# design.net
KiCad netlist of a schematic drawn in Altium Designer
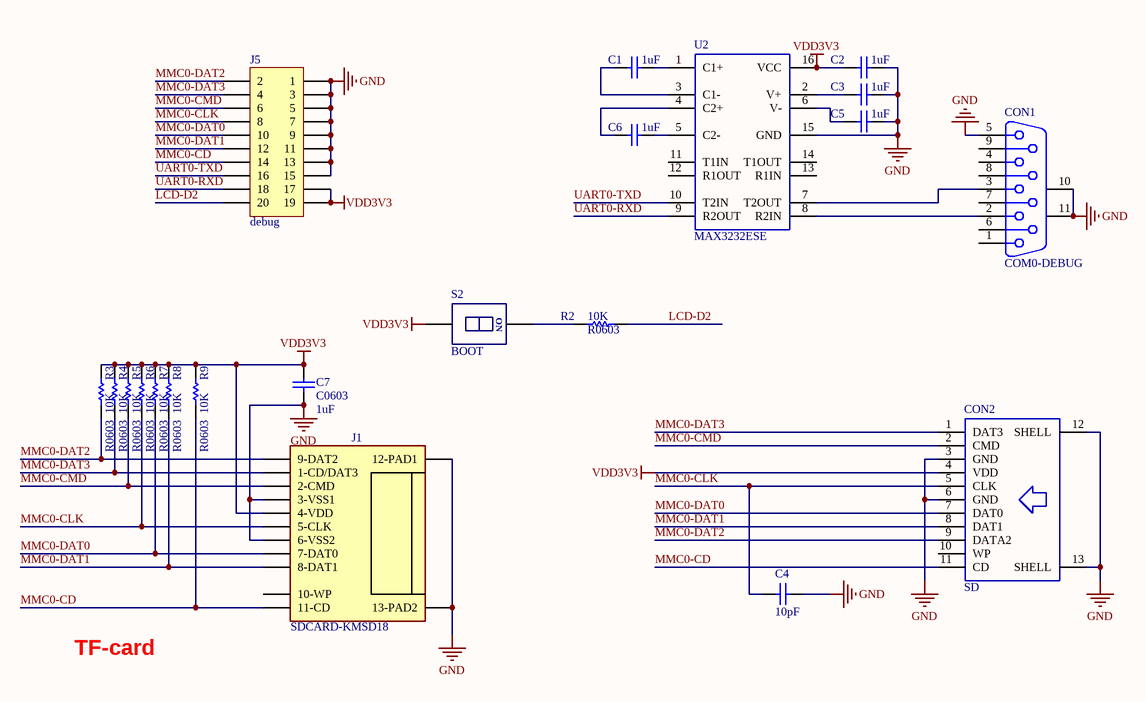
[diagram p0: 调试烧写.SchDoc]

(export (version "E")
  (design (tool "Eeschema 10.0.6"))
  (components
    (comp (ref "C1")
      (value "1uF")
      (footprint "C0603_M1608")
      (description "Capacitor")
      (fields (field (name "Comment") "Cap") (field (name "PUBLISHER") "Altium Limited"))
      (libsource (lib "Miscellaneous Devices") (part "Cap"))
    )
    (comp (ref "C2")
      (value "1uF")
      (footprint "C0603_M1608")
      (description "Capacitor")
      (fields (field (name "Comment") "Cap") (field (name "PUBLISHER") "Altium Limited"))
      (libsource (lib "Miscellaneous Devices") (part "Cap"))
    )
    (comp (ref "C3")
      (value "1uF")
      (footprint "C0603_M1608")
      (description "Capacitor")
      (fields (field (name "Comment") "Cap") (field (name "PUBLISHER") "Altium Limited"))
      (libsource (lib "Miscellaneous Devices") (part "Cap"))
    )
    (comp (ref "C4")
      (value "10pF")
      (footprint "C0603_M1608")
      (description "Capacitor")
      (fields (field (name "Comment") "Cap") (field (name "PUBLISHER") "Altium Limited"))
      (libsource (lib "Miscellaneous Devices") (part "Cap"))
    )
    (comp (ref "C5")
      (value "1uF")
      (footprint "C0603_M1608")
      (description "Capacitor")
      (fields (field (name "Comment") "Cap") (field (name "PUBLISHER") "Altium Limited"))
      (libsource (lib "Miscellaneous Devices") (part "Cap"))
    )
    (comp (ref "C6")
      (value "1uF")
      (footprint "C0603_M1608")
      (description "Capacitor")
      (fields (field (name "Comment") "Cap") (field (name "PUBLISHER") "Altium Limited"))
      (libsource (lib "Miscellaneous Devices") (part "Cap"))
    )
    (comp (ref "C7")
      (value "C0603")
      (description "Capacitor")
      (fields (field (name "ALTIUM_VALUE") "1uF") (field (name "PUBLISHER") "Altium Limited"))
      (libsource (lib "Miscellaneous Devices") (part "Cap"))
    )
    (comp (ref "CON1")
      (value "COM0-DEBUG")
      (footprint "DSUB1.385-2H9-M")
      (description "Receptacle Assembly, 9 Position, Right Angle")
      (fields (field (name "PUBLISHER") "Altium Limited"))
      (libsource (lib "Miscellaneous Connectors") (part "D Connector 9"))
    )
    (comp (ref "CON2") (value "SD") (footprint "SD-CARD3") (libsource (lib "Sch") (part "SD")))
    (comp (ref "J1")
      (value "SDCARD-KMSD18")
      (footprint "TF-CARD")
      (libsource (lib "Miscellaneous Connectors") (part "SDCARD_KMSD18"))
    )
    (comp (ref "J5")
      (value "debug")
      (description "Header, 10-Pin, Dual row")
      (fields (field (name "PUBLISHER") "Altium Limited"))
      (libsource (lib "Miscellaneous Connectors") (part "Header 10X2"))
    )
    (comp (ref "R2")
      (value "R0603")
      (description "Resistor")
      (fields (field (name "ALTIUM_VALUE") "10K") (field (name "PUBLISHER") "Altium Limited"))
      (libsource (lib "Miscellaneous Devices") (part "Res1"))
    )
    (comp (ref "R3")
      (value "R0603")
      (description "Resistor")
      (fields (field (name "ALTIUM_VALUE") "10K") (field (name "PUBLISHER") "Altium Limited"))
      (libsource (lib "Miscellaneous Devices") (part "Res1"))
    )
    (comp (ref "R4")
      (value "R0603")
      (description "Resistor")
      (fields (field (name "ALTIUM_VALUE") "10K") (field (name "PUBLISHER") "Altium Limited"))
      (libsource (lib "Miscellaneous Devices") (part "Res1"))
    )
    (comp (ref "R5")
      (value "R0603")
      (description "Resistor")
      (fields (field (name "ALTIUM_VALUE") "10K") (field (name "PUBLISHER") "Altium Limited"))
      (libsource (lib "Miscellaneous Devices") (part "Res1"))
    )
    (comp (ref "R6")
      (value "R0603")
      (description "Resistor")
      (fields (field (name "ALTIUM_VALUE") "10K") (field (name "PUBLISHER") "Altium Limited"))
      (libsource (lib "Miscellaneous Devices") (part "Res1"))
    )
    (comp (ref "R7")
      (value "R0603")
      (description "Resistor")
      (fields (field (name "ALTIUM_VALUE") "10K") (field (name "PUBLISHER") "Altium Limited"))
      (libsource (lib "Miscellaneous Devices") (part "Res1"))
    )
    (comp (ref "R8")
      (value "R0603")
      (description "Resistor")
      (fields (field (name "ALTIUM_VALUE") "10K") (field (name "PUBLISHER") "Altium Limited"))
      (libsource (lib "Miscellaneous Devices") (part "Res1"))
    )
    (comp (ref "R9")
      (value "R0603")
      (description "Resistor")
      (fields (field (name "ALTIUM_VALUE") "10K") (field (name "PUBLISHER") "Altium Limited"))
      (libsource (lib "Miscellaneous Devices") (part "Res1"))
    )
    (comp (ref "S2")
      (value "BOOT")
      (footprint "SWITCH_1P")
      (libsource (lib "Miscellaneous Connectors") (part "SW DIP-1"))
    )
    (comp (ref "U2") (value "MAX3232ESE") (footprint "SOIC-16N") (libsource (lib "Sch") (part "MAX3232")))
  )
  (nets
    (net (code "1") (name "/LCD-D2") (class "Default")
      (node (ref "J5") (pin "20") (pinfunction "20_20") (pintype "passive"))
      (node (ref "R2") (pin "2") (pinfunction "2_2") (pintype "passive"))
    )
    (net (code "2") (name "/MMC0-CD") (class "Default")
      (node (ref "CON2") (pin "11") (pinfunction "CD_11") (pintype "passive"))
      (node (ref "J1") (pin "11") (pinfunction "11-CD_11") (pintype "passive"))
      (node (ref "J5") (pin "14") (pinfunction "14_14") (pintype "passive"))
      (node (ref "R9") (pin "1") (pinfunction "1_1") (pintype "passive"))
    )
    (net (code "3") (name "/MMC0-CLK") (class "Default")
      (node (ref "C4") (pin "2") (pinfunction "2_2") (pintype "passive"))
      (node (ref "CON2") (pin "5") (pinfunction "CLK_5") (pintype "passive"))
      (node (ref "J1") (pin "5") (pinfunction "5-CLK_5") (pintype "passive"))
      (node (ref "J5") (pin "8") (pinfunction "8_8") (pintype "passive"))
      (node (ref "R6") (pin "1") (pinfunction "1_1") (pintype "passive"))
    )
    (net (code "4") (name "/MMC0-CMD") (class "Default")
      (node (ref "CON2") (pin "2") (pinfunction "CMD_2") (pintype "passive"))
      (node (ref "J1") (pin "2") (pinfunction "2-CMD_2") (pintype "passive"))
      (node (ref "J5") (pin "6") (pinfunction "6_6") (pintype "passive"))
      (node (ref "R5") (pin "1") (pinfunction "1_1") (pintype "passive"))
    )
    (net (code "5") (name "/MMC0-DAT0") (class "Default")
      (node (ref "CON2") (pin "7") (pinfunction "DAT0_7") (pintype "passive"))
      (node (ref "J1") (pin "7") (pinfunction "7-DAT0_7") (pintype "passive"))
      (node (ref "J5") (pin "10") (pinfunction "10_10") (pintype "passive"))
      (node (ref "R7") (pin "1") (pinfunction "1_1") (pintype "passive"))
    )
    (net (code "6") (name "/MMC0-DAT1") (class "Default")
      (node (ref "CON2") (pin "8") (pinfunction "DAT1_8") (pintype "passive"))
      (node (ref "J1") (pin "8") (pinfunction "8-DAT1_8") (pintype "passive"))
      (node (ref "J5") (pin "12") (pinfunction "12_12") (pintype "passive"))
      (node (ref "R8") (pin "1") (pinfunction "1_1") (pintype "passive"))
    )
    (net (code "7") (name "/MMC0-DAT2") (class "Default")
      (node (ref "CON2") (pin "9") (pinfunction "DATA2_9") (pintype "passive"))
      (node (ref "J1") (pin "9") (pinfunction "9-DAT2_9") (pintype "passive"))
      (node (ref "J5") (pin "2") (pinfunction "2_2") (pintype "passive"))
      (node (ref "R3") (pin "1") (pinfunction "1_1") (pintype "passive"))
    )
    (net (code "8") (name "/MMC0-DAT3") (class "Default")
      (node (ref "CON2") (pin "1") (pinfunction "DAT3_1") (pintype "passive"))
      (node (ref "J1") (pin "1") (pinfunction "1-CD/DAT3_1") (pintype "passive"))
      (node (ref "J5") (pin "4") (pinfunction "4_4") (pintype "passive"))
      (node (ref "R4") (pin "1") (pinfunction "1_1") (pintype "passive"))
    )
    (net (code "9") (name "/UART0-RXD") (class "Default")
      (node (ref "J5") (pin "18") (pinfunction "18_18") (pintype "passive"))
      (node (ref "U2") (pin "9") (pinfunction "R2OUT_9") (pintype "passive"))
    )
    (net (code "10") (name "/UART0-TXD") (class "Default")
      (node (ref "J5") (pin "16") (pinfunction "16_16") (pintype "passive"))
      (node (ref "U2") (pin "10") (pinfunction "T2IN_10") (pintype "passive"))
    )
    (net (code "11") (name "GND") (class "Default")
      (node (ref "C2") (pin "1") (pinfunction "1_1") (pintype "passive"))
      (node (ref "C3") (pin "1") (pinfunction "1_1") (pintype "passive"))
      (node (ref "C4") (pin "1") (pinfunction "1_1") (pintype "passive"))
      (node (ref "C5") (pin "1") (pinfunction "1_1") (pintype "passive"))
      (node (ref "C7") (pin "1") (pinfunction "1_1") (pintype "passive"))
      (node (ref "CON1") (pin "10") (pinfunction "MH1_10") (pintype "passive"))
      (node (ref "CON1") (pin "11") (pinfunction "MH2_11") (pintype "passive"))
      (node (ref "CON1") (pin "5") (pinfunction "5_5") (pintype "passive"))
      (node (ref "CON2") (pin "12") (pinfunction "SHELL_12") (pintype "passive"))
      (node (ref "CON2") (pin "13") (pinfunction "SHELL_13") (pintype "passive"))
      (node (ref "CON2") (pin "3") (pinfunction "GND_3") (pintype "passive"))
      (node (ref "CON2") (pin "6") (pinfunction "GND_6") (pintype "passive"))
      (node (ref "J1") (pin "12") (pinfunction "12-PAD1_12") (pintype "passive"))
      (node (ref "J1") (pin "13") (pinfunction "13-PAD2_13") (pintype "passive"))
      (node (ref "J1") (pin "3") (pinfunction "3-VSS1_3") (pintype "passive"))
      (node (ref "J1") (pin "6") (pinfunction "6-VSS2_6") (pintype "passive"))
      (node (ref "J5") (pin "1") (pinfunction "1_1") (pintype "passive"))
      (node (ref "J5") (pin "11") (pinfunction "11_11") (pintype "passive"))
      (node (ref "J5") (pin "13") (pinfunction "13_13") (pintype "passive"))
      (node (ref "J5") (pin "15") (pinfunction "15_15") (pintype "passive"))
      (node (ref "J5") (pin "3") (pinfunction "3_3") (pintype "passive"))
      (node (ref "J5") (pin "5") (pinfunction "5_5") (pintype "passive"))
      (node (ref "J5") (pin "7") (pinfunction "7_7") (pintype "passive"))
      (node (ref "J5") (pin "9") (pinfunction "9_9") (pintype "passive"))
      (node (ref "U2") (pin "15") (pinfunction "GND_15") (pintype "passive"))
    )
    (net (code "12") (name "Net-(R2-Pad1)") (class "Default")
      (node (ref "R2") (pin "1") (pinfunction "1_1") (pintype "passive"))
      (node (ref "S2") (pin "2") (pinfunction "2_2") (pintype "passive"))
    )
    (net (code "13") (name "Net-(U2-C1+)") (class "Default")
      (node (ref "C1") (pin "1") (pinfunction "1_1") (pintype "passive"))
      (node (ref "U2") (pin "1") (pinfunction "C1+_1") (pintype "passive"))
    )
    (net (code "14") (name "Net-(U2-C1-)") (class "Default")
      (node (ref "C1") (pin "2") (pinfunction "2_2") (pintype "passive"))
      (node (ref "U2") (pin "3") (pinfunction "C1-_3") (pintype "passive"))
    )
    (net (code "15") (name "Net-(U2-C2+)") (class "Default")
      (node (ref "C6") (pin "2") (pinfunction "2_2") (pintype "passive"))
      (node (ref "U2") (pin "4") (pinfunction "C2+_4") (pintype "passive"))
    )
    (net (code "16") (name "Net-(U2-C2-)") (class "Default")
      (node (ref "C6") (pin "1") (pinfunction "1_1") (pintype "passive"))
      (node (ref "U2") (pin "5") (pinfunction "C2-_5") (pintype "passive"))
    )
    (net (code "17") (name "Net-(U2-R2IN)") (class "Default")
      (node (ref "CON1") (pin "2") (pinfunction "2_2") (pintype "passive"))
      (node (ref "U2") (pin "8") (pinfunction "R2IN_8") (pintype "passive"))
    )
    (net (code "18") (name "Net-(U2-T2OUT)") (class "Default")
      (node (ref "CON1") (pin "3") (pinfunction "3_3") (pintype "passive"))
      (node (ref "U2") (pin "7") (pinfunction "T2OUT_7") (pintype "passive"))
    )
    (net (code "19") (name "Net-(U2-V+)") (class "Default")
      (node (ref "C3") (pin "2") (pinfunction "2_2") (pintype "passive"))
      (node (ref "U2") (pin "2") (pinfunction "V+_2") (pintype "passive"))
    )
    (net (code "20") (name "Net-(U2-V-)") (class "Default")
      (node (ref "C5") (pin "2") (pinfunction "2_2") (pintype "passive"))
      (node (ref "U2") (pin "6") (pinfunction "V-_6") (pintype "passive"))
    )
    (net (code "21") (name "VDD3V3") (class "Default")
      (node (ref "C2") (pin "2") (pinfunction "2_2") (pintype "passive"))
      (node (ref "C7") (pin "2") (pinfunction "2_2") (pintype "passive"))
      (node (ref "CON2") (pin "4") (pinfunction "VDD_4") (pintype "passive"))
      (node (ref "J1") (pin "4") (pinfunction "4-VDD_4") (pintype "passive"))
      (node (ref "J5") (pin "17") (pinfunction "17_17") (pintype "passive"))
      (node (ref "J5") (pin "19") (pinfunction "19_19") (pintype "passive"))
      (node (ref "R3") (pin "2") (pinfunction "2_2") (pintype "passive"))
      (node (ref "R4") (pin "2") (pinfunction "2_2") (pintype "passive"))
      (node (ref "R5") (pin "2") (pinfunction "2_2") (pintype "passive"))
      (node (ref "R6") (pin "2") (pinfunction "2_2") (pintype "passive"))
      (node (ref "R7") (pin "2") (pinfunction "2_2") (pintype "passive"))
      (node (ref "R8") (pin "2") (pinfunction "2_2") (pintype "passive"))
      (node (ref "R9") (pin "2") (pinfunction "2_2") (pintype "passive"))
      (node (ref "S2") (pin "1") (pinfunction "1_1") (pintype "passive"))
      (node (ref "U2") (pin "16") (pinfunction "VCC_16") (pintype "passive"))
    )
    (net (code "22") (name "unconnected-(CON1-Pad1)") (class "Default")
      (node (ref "CON1") (pin "1") (pinfunction "1_1") (pintype "passive"))
    )
    (net (code "23") (name "unconnected-(CON1-Pad4)") (class "Default")
      (node (ref "CON1") (pin "4") (pinfunction "4_4") (pintype "passive"))
    )
    (net (code "24") (name "unconnected-(CON1-Pad6)") (class "Default")
      (node (ref "CON1") (pin "6") (pinfunction "6_6") (pintype "passive"))
    )
    (net (code "25") (name "unconnected-(CON1-Pad7)") (class "Default")
      (node (ref "CON1") (pin "7") (pinfunction "7_7") (pintype "passive"))
    )
    (net (code "26") (name "unconnected-(CON1-Pad8)") (class "Default")
      (node (ref "CON1") (pin "8") (pinfunction "8_8") (pintype "passive"))
    )
    (net (code "27") (name "unconnected-(CON1-Pad9)") (class "Default")
      (node (ref "CON1") (pin "9") (pinfunction "9_9") (pintype "passive"))
    )
    (net (code "28") (name "unconnected-(CON2-WP-Pad10)") (class "Default")
      (node (ref "CON2") (pin "10") (pinfunction "WP_10") (pintype "passive"))
    )
    (net (code "29") (name "unconnected-(J1-10-WP-Pad10)") (class "Default")
      (node (ref "J1") (pin "10") (pinfunction "10-WP_10") (pintype "passive"))
    )
    (net (code "30") (name "unconnected-(U2-R1IN-Pad13)") (class "Default")
      (node (ref "U2") (pin "13") (pinfunction "R1IN_13") (pintype "passive"))
    )
    (net (code "31") (name "unconnected-(U2-R1OUT-Pad12)") (class "Default")
      (node (ref "U2") (pin "12") (pinfunction "R1OUT_12") (pintype "passive"))
    )
    (net (code "32") (name "unconnected-(U2-T1IN-Pad11)") (class "Default")
      (node (ref "U2") (pin "11") (pinfunction "T1IN_11") (pintype "passive"))
    )
    (net (code "33") (name "unconnected-(U2-T1OUT-Pad14)") (class "Default")
      (node (ref "U2") (pin "14") (pinfunction "T1OUT_14") (pintype "passive"))
    )
  )
)
